# mcu.net
KiCad netlist of a schematic drawn in Altium Designer
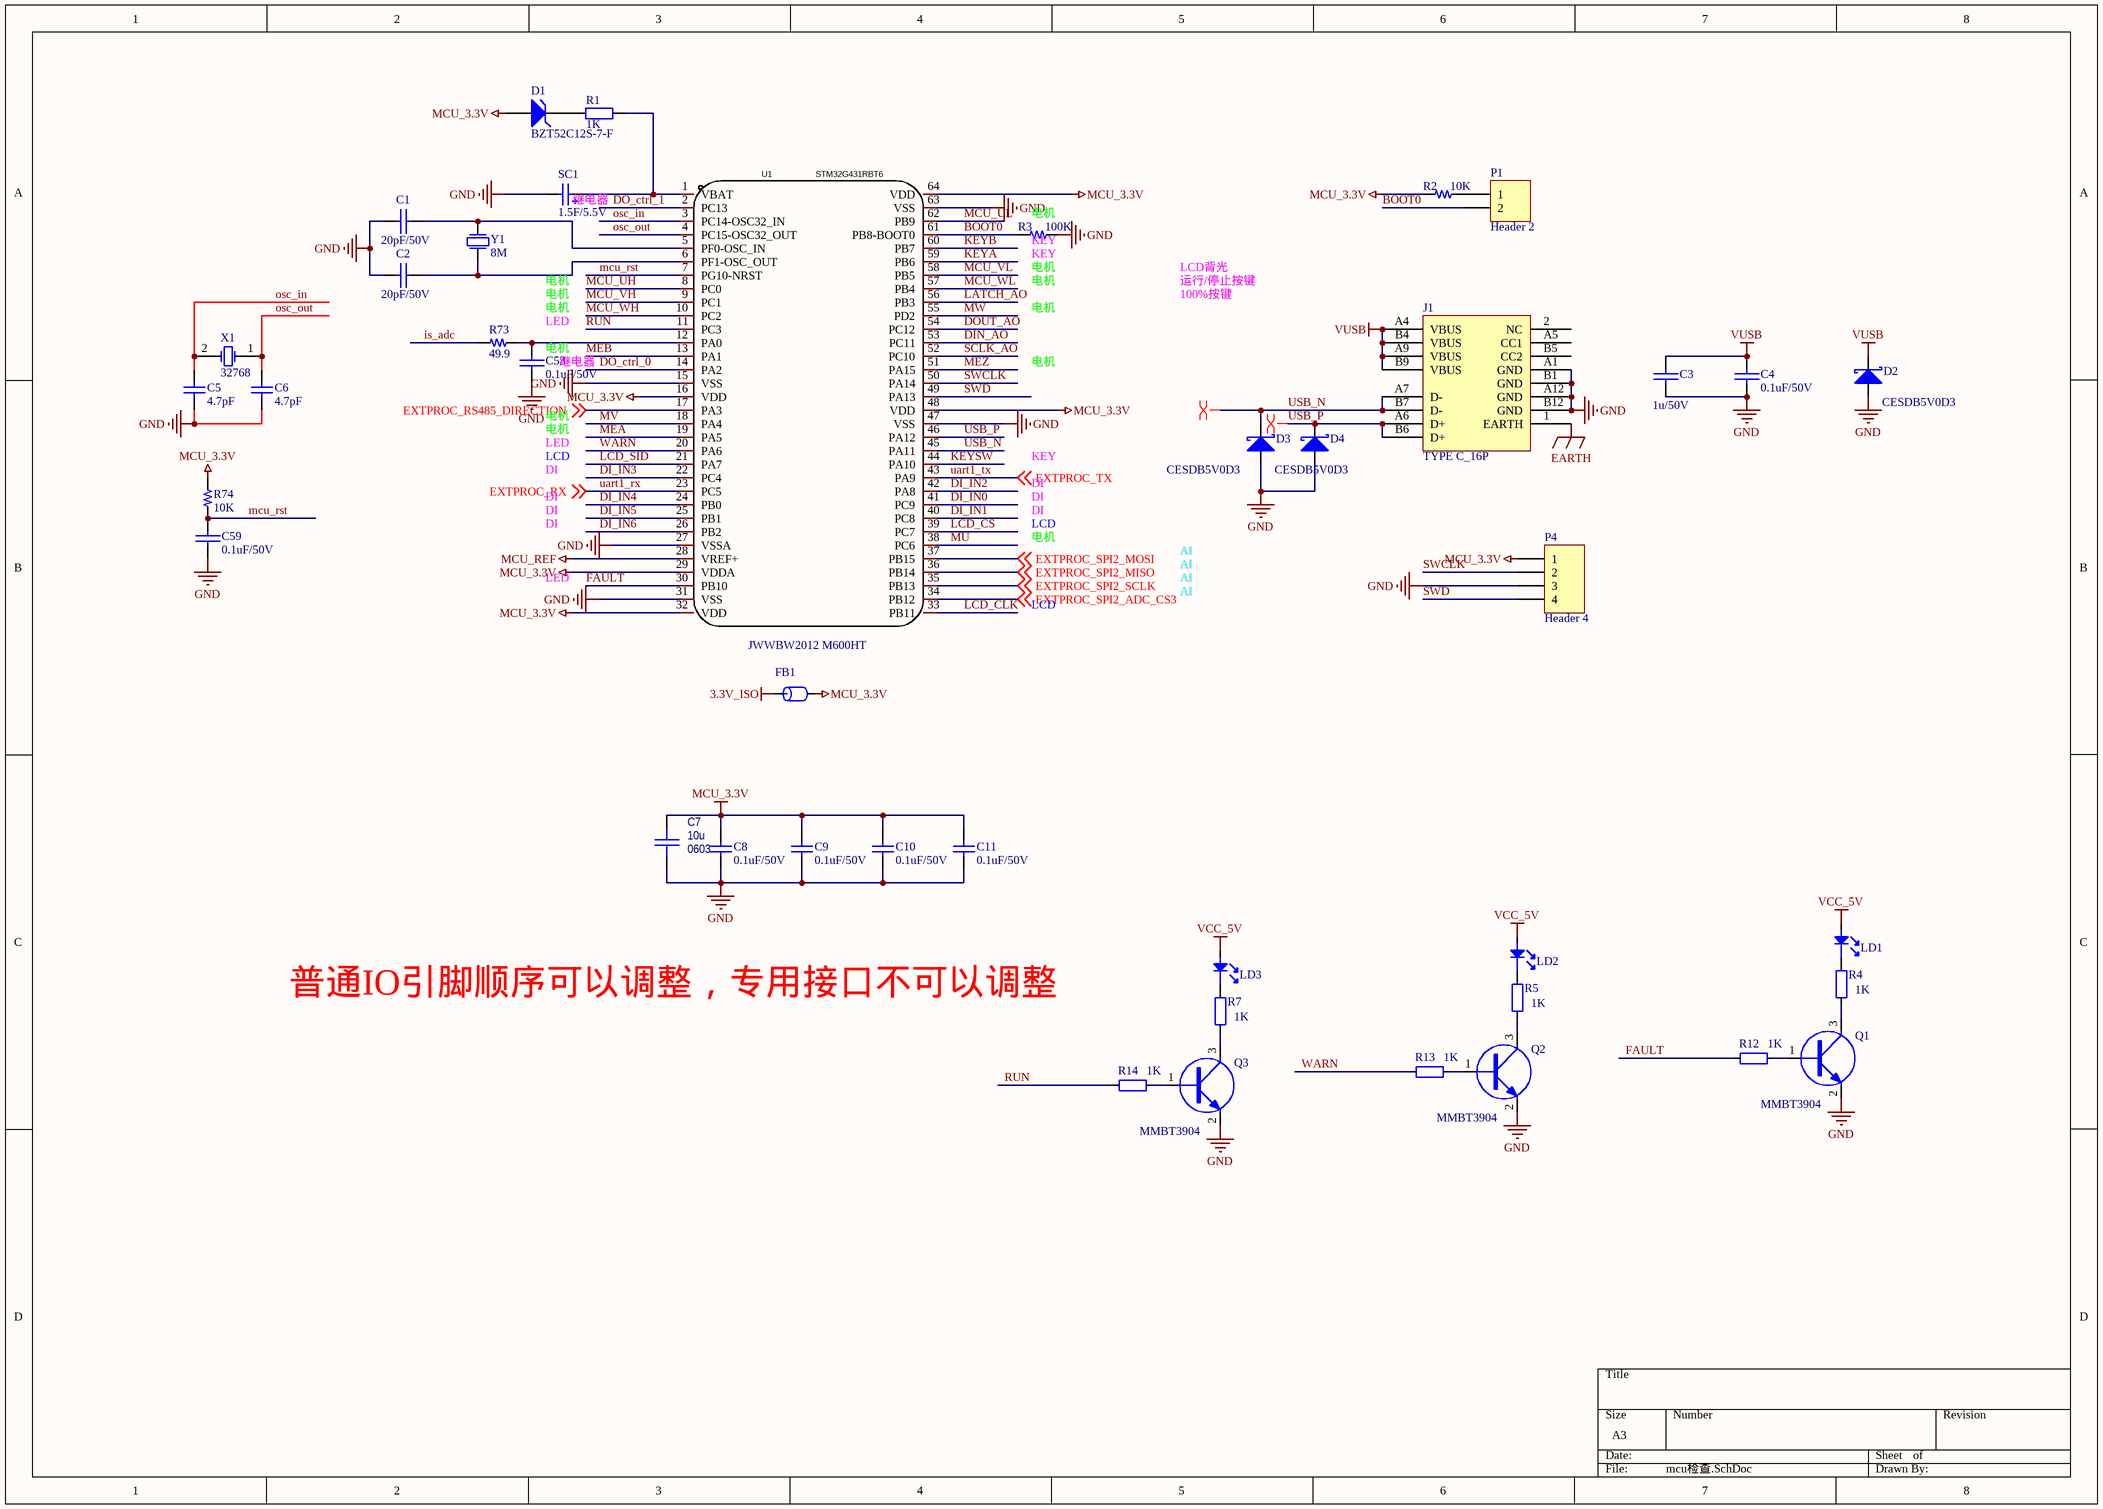
[diagram p0: mcu检查.SchDoc]

(export (version "E")
  (design (tool "Eeschema 10.0.6"))
  (components
    (comp (ref "C1")
      (value "20pF/50V")
      (footprint "0603C")
      (fields (field (name "Comment") "20pF/25V"))
      (libsource (lib "SM") (part "CAP"))
    )
    (comp (ref "C2")
      (value "20pF/50V")
      (footprint "0603C")
      (fields (field (name "Comment") "20pF/25V"))
      (libsource (lib "SM") (part "CAP"))
    )
    (comp (ref "C3")
      (value "1u/50V")
      (footprint "0603C")
      (fields (field (name "Comment") "1uF/25V"))
      (libsource (lib "SM") (part "CAP"))
    )
    (comp (ref "C4") (value "0.1uF/50V") (footprint "0603C") (libsource (lib "SM") (part "CAP")))
    (comp (ref "C5")
      (value "4.7pF")
      (footprint "0603C")
      (description "Capacitor")
      (fields (field (name "PUBLISHER") "Altium Limited"))
      (libsource (lib "Miscellaneous Devices") (part "Cap"))
    )
    (comp (ref "C6")
      (value "4.7pF")
      (footprint "0603C")
      (description "Capacitor")
      (fields (field (name "PUBLISHER") "Altium Limited"))
      (libsource (lib "Miscellaneous Devices") (part "Cap"))
    )
    (comp (ref "C7")
      (value "10u")
      (footprint "CAPC1608X092N_0603")
      (description "Capacitor, MLCC")
      (fields
        (field (name "MANUFACTURER") "Murata Electronics")
        (field (name "PARTNUMBER") "GRM188R61A106KE69D")
        (field (name "PACKAGE") "0603")
      )
      (libsource (lib "Karl") (part "Capacitor_0603"))
    )
    (comp (ref "C8")
      (value "0.1uF/50V")
      (footprint "0603C")
      (description "Capacitor")
      (fields (field (name "PUBLISHER") "Altium Limited"))
      (libsource (lib "Miscellaneous Devices") (part "Cap"))
    )
    (comp (ref "C9")
      (value "0.1uF/50V")
      (footprint "0603C")
      (description "Capacitor")
      (fields (field (name "PUBLISHER") "Altium Limited"))
      (libsource (lib "Miscellaneous Devices") (part "Cap"))
    )
    (comp (ref "C10")
      (value "0.1uF/50V")
      (footprint "0603C")
      (description "Capacitor")
      (fields (field (name "PUBLISHER") "Altium Limited"))
      (libsource (lib "Miscellaneous Devices") (part "Cap"))
    )
    (comp (ref "C11")
      (value "0.1uF/50V")
      (footprint "0603C")
      (description "Capacitor")
      (fields (field (name "PUBLISHER") "Altium Limited"))
      (libsource (lib "Miscellaneous Devices") (part "Cap"))
    )
    (comp (ref "C53") (value "0.1uF/50V") (footprint "0603C") (libsource (lib "SM") (part "CAP")))
    (comp (ref "C59") (value "0.1uF/50V") (footprint "0603C") (libsource (lib "SM") (part "CAP")))
    (comp (ref "D1")
      (value "BZT52C12S-7-F")
      (footprint "DIOD-SOD323-2_V")
      (libsource (lib "Bogen") (part "BZT52C12S-7-F"))
    )
    (comp (ref "D2") (value "CESDB5V0D3") (footprint "SOD323") (libsource (lib "*") (part "DIODE S")))
    (comp (ref "D3") (value "CESDB5V0D3") (footprint "SOD323") (libsource (lib "*") (part "DIODE S")))
    (comp (ref "D4") (value "CESDB5V0D3") (footprint "SOD323") (libsource (lib "*") (part "DIODE S")))
    (comp (ref "FB1")
      (value "JWWBW2012 M600HT")
      (footprint "0805R")
      (libsource (lib "Schlib_20110825") (part "FB"))
    )
    (comp (ref "J1")
      (value "TYPE C_16P")
      (footprint "TYPEC_16P")
      (libsource (lib "Schlib_20110825") (part "TYPE C_16P"))
    )
    (comp (ref "LD1")
      (value "LED_Green_19-217")
      (footprint "0603led")
      (libsource (lib "RC_M_D_00") (part "LED_Green_19-217"))
    )
    (comp (ref "LD2")
      (value "LED_Green_19-217")
      (footprint "0603led")
      (libsource (lib "RC_M_D_00") (part "LED_Green_19-217"))
    )
    (comp (ref "LD3")
      (value "LED_Green_19-217")
      (footprint "0603led")
      (libsource (lib "RC_M_D_00") (part "LED_Green_19-217"))
    )
    (comp (ref "P1")
      (value "Header 2")
      (footprint "HDR1X2")
      (fields (field (name "PUBLISHER") "Altium Limited"))
      (libsource (lib "Miscellaneous Connectors") (part "Header 2"))
    )
    (comp (ref "P4")
      (value "Header 4")
      (footprint "HDR1X4")
      (fields (field (name "PUBLISHER") "Altium Limited"))
      (libsource (lib "Miscellaneous Connectors") (part "Header 4"))
    )
    (comp (ref "Q1")
      (value "MMBT3904")
      (footprint "SOT23-3")
      (libsource (lib "CenLib") (part "NPN_MMBT3904"))
    )
    (comp (ref "Q2")
      (value "MMBT3904")
      (footprint "SOT23-3")
      (libsource (lib "CenLib") (part "NPN_MMBT3904"))
    )
    (comp (ref "Q3")
      (value "MMBT3904")
      (footprint "SOT23-3")
      (libsource (lib "CenLib") (part "NPN_MMBT3904"))
    )
    (comp (ref "R1") (value "1K") (footprint "0603R") (libsource (lib "MQlibrary") (part "Res0805M")))
    (comp (ref "R2") (value "10K") (footprint "0603R") (libsource (lib "JRJ_1") (part "R")))
    (comp (ref "R3") (value "100K") (footprint "0603R") (libsource (lib "JRJ_1") (part "R")))
    (comp (ref "R4") (value "1K") (footprint "0603r") (libsource (lib "RC_M_D_00") (part "RES0603")))
    (comp (ref "R5") (value "1K") (footprint "0603r") (libsource (lib "RC_M_D_00") (part "RES0603")))
    (comp (ref "R7") (value "1K") (footprint "0603r") (libsource (lib "RC_M_D_00") (part "RES0603")))
    (comp (ref "R12") (value "1K") (footprint "0603r") (libsource (lib "RC_M_D_00") (part "RES0603")))
    (comp (ref "R13") (value "1K") (footprint "0603r") (libsource (lib "RC_M_D_00") (part "RES0603")))
    (comp (ref "R14") (value "1K") (footprint "0603r") (libsource (lib "RC_M_D_00") (part "RES0603")))
    (comp (ref "R73") (value "49.9") (footprint "0603R") (libsource (lib "JRJ_1") (part "R")))
    (comp (ref "R74") (value "10K") (footprint "0603R") (libsource (lib "JRJ_1") (part "R")))
    (comp (ref "SC1")
      (value "1.5F/5.5V")
      (footprint "CAP-TH_DMS3R3224")
      (description "Polarized Capacitor (Axial)")
      (fields (field (name "PUBLISHER") "Altium Limited"))
      (libsource (lib "Miscellaneous Devices") (part "Cap Pol2"))
    )
    (comp (ref "U1")
      (value "STM32G431RBT6")
      (footprint "LQFP-64")
      (fields (field (name "MANUFACTURER") "ST(意法半导体)"))
      (libsource (lib "altium-import") (part "root_0_STM32G431RBT6_"))
    )
    (comp (ref "X1")
      (value "32768")
      (footprint "A")
      (description "Crystal Oscillator")
      (fields (field (name "PUBLISHER") "Altium Limited"))
      (libsource (lib "Miscellaneous Devices") (part "XTAL"))
    )
    (comp (ref "Y1") (value "8M") (footprint "CRAY_5032") (libsource (lib "") (part "XTAL_1")))
  )
  (nets
    (net (code "1") (name "/BOOT0") (class "Default")
      (node (ref "P1") (pin "2") (pinfunction "2_2") (pintype "passive"))
      (node (ref "R3") (pin "1") (pintype "passive"))
      (node (ref "U1") (pin "61") (pinfunction "PB8-BOOT0_61") (pintype "passive"))
    )
    (net (code "2") (name "/DIN_AO") (class "Default")
      (node (ref "U1") (pin "53") (pinfunction "PC11_53") (pintype "passive"))
    )
    (net (code "3") (name "/DI_IN0") (class "Default")
      (node (ref "U1") (pin "41") (pinfunction "PC9_41") (pintype "passive"))
    )
    (net (code "4") (name "/DI_IN1") (class "Default")
      (node (ref "U1") (pin "40") (pinfunction "PC8_40") (pintype "passive"))
    )
    (net (code "5") (name "/DI_IN2") (class "Default")
      (node (ref "U1") (pin "42") (pinfunction "PA8_42") (pintype "passive"))
    )
    (net (code "6") (name "/DI_IN3") (class "Default")
      (node (ref "U1") (pin "22") (pinfunction "PC4_22") (pintype "passive"))
    )
    (net (code "7") (name "/DI_IN4") (class "Default")
      (node (ref "U1") (pin "24") (pinfunction "PB0_24") (pintype "passive"))
    )
    (net (code "8") (name "/DI_IN5") (class "Default")
      (node (ref "U1") (pin "25") (pinfunction "PB1_25") (pintype "passive"))
    )
    (net (code "9") (name "/DI_IN6") (class "Default")
      (node (ref "U1") (pin "26") (pinfunction "PB2_26") (pintype "passive"))
    )
    (net (code "10") (name "/DOUT_AO") (class "Default")
      (node (ref "U1") (pin "54") (pinfunction "PC12_54") (pintype "passive"))
    )
    (net (code "11") (name "/DO_ctrl_0") (class "Default")
      (node (ref "U1") (pin "14") (pinfunction "PA2_14") (pintype "passive"))
    )
    (net (code "12") (name "/DO_ctrl_1") (class "Default")
      (node (ref "U1") (pin "2") (pinfunction "PC13_2") (pintype "passive"))
    )
    (net (code "13") (name "/FAULT") (class "Default")
      (node (ref "R12") (pin "1") (pinfunction "1_1") (pintype "passive"))
      (node (ref "U1") (pin "30") (pinfunction "PB10_30") (pintype "passive"))
    )
    (net (code "14") (name "/KEYA") (class "Default")
      (node (ref "U1") (pin "59") (pinfunction "PB6_59") (pintype "passive"))
    )
    (net (code "15") (name "/KEYB") (class "Default")
      (node (ref "U1") (pin "60") (pinfunction "PB7_60") (pintype "passive"))
    )
    (net (code "16") (name "/KEYSW") (class "Default")
      (node (ref "U1") (pin "44") (pinfunction "PA10_44") (pintype "passive"))
    )
    (net (code "17") (name "/LATCH_AO") (class "Default")
      (node (ref "U1") (pin "56") (pinfunction "PB3_56") (pintype "passive"))
    )
    (net (code "18") (name "/LCD_CLK") (class "Default")
      (node (ref "U1") (pin "33") (pinfunction "PB11_33") (pintype "passive"))
    )
    (net (code "19") (name "/LCD_CS") (class "Default")
      (node (ref "U1") (pin "39") (pinfunction "PC7_39") (pintype "passive"))
    )
    (net (code "20") (name "/LCD_SID") (class "Default")
      (node (ref "U1") (pin "21") (pinfunction "PA7_21") (pintype "passive"))
    )
    (net (code "21") (name "/MCU_UH") (class "Default")
      (node (ref "U1") (pin "8") (pinfunction "PC0_8") (pintype "passive"))
    )
    (net (code "22") (name "/MCU_UL") (class "Default")
      (node (ref "U1") (pin "62") (pinfunction "PB9_62") (pintype "passive"))
    )
    (net (code "23") (name "/MCU_VH") (class "Default")
      (node (ref "U1") (pin "9") (pinfunction "PC1_9") (pintype "passive"))
    )
    (net (code "24") (name "/MCU_VL") (class "Default")
      (node (ref "U1") (pin "58") (pinfunction "PB5_58") (pintype "passive"))
    )
    (net (code "25") (name "/MCU_WH") (class "Default")
      (node (ref "U1") (pin "10") (pinfunction "PC2_10") (pintype "passive"))
    )
    (net (code "26") (name "/MCU_WL") (class "Default")
      (node (ref "U1") (pin "57") (pinfunction "PB4_57") (pintype "passive"))
    )
    (net (code "27") (name "/MEA") (class "Default")
      (node (ref "U1") (pin "19") (pinfunction "PA5_19") (pintype "passive"))
    )
    (net (code "28") (name "/MEB") (class "Default")
      (node (ref "U1") (pin "13") (pinfunction "PA1_13") (pintype "passive"))
    )
    (net (code "29") (name "/MEZ") (class "Default")
      (node (ref "U1") (pin "51") (pinfunction "PA15_51") (pintype "passive"))
    )
    (net (code "30") (name "/MU") (class "Default")
      (node (ref "U1") (pin "38") (pinfunction "PC6_38") (pintype "passive"))
    )
    (net (code "31") (name "/MV") (class "Default")
      (node (ref "U1") (pin "18") (pinfunction "PA4_18") (pintype "passive"))
    )
    (net (code "32") (name "/MW") (class "Default")
      (node (ref "U1") (pin "55") (pinfunction "PD2_55") (pintype "passive"))
    )
    (net (code "33") (name "/RUN") (class "Default")
      (node (ref "R14") (pin "1") (pinfunction "1_1") (pintype "passive"))
      (node (ref "U1") (pin "11") (pinfunction "PC3_11") (pintype "passive"))
    )
    (net (code "34") (name "/SCLK_AO") (class "Default")
      (node (ref "U1") (pin "52") (pinfunction "PC10_52") (pintype "passive"))
    )
    (net (code "35") (name "/SWCLK") (class "Default")
      (node (ref "P4") (pin "2") (pinfunction "2_2") (pintype "passive"))
      (node (ref "U1") (pin "50") (pinfunction "PA14_50") (pintype "passive"))
    )
    (net (code "36") (name "/SWD") (class "Default")
      (node (ref "P4") (pin "4") (pinfunction "4_4") (pintype "passive"))
      (node (ref "U1") (pin "49") (pinfunction "PA13_49") (pintype "passive"))
    )
    (net (code "37") (name "/USB_N") (class "Default")
      (node (ref "D3") (pin "2") (pinfunction "K_2") (pintype "passive"))
      (node (ref "J1") (pin "A7") (pinfunction "D-_A7") (pintype "passive"))
      (node (ref "J1") (pin "B7") (pinfunction "D-_B7") (pintype "passive"))
      (node (ref "U1") (pin "45") (pinfunction "PA11_45") (pintype "passive"))
    )
    (net (code "38") (name "/USB_P") (class "Default")
      (node (ref "D4") (pin "2") (pinfunction "K_2") (pintype "passive"))
      (node (ref "J1") (pin "A6") (pinfunction "D+_A6") (pintype "passive"))
      (node (ref "J1") (pin "B6") (pinfunction "D+_B6") (pintype "passive"))
      (node (ref "U1") (pin "46") (pinfunction "PA12_46") (pintype "passive"))
    )
    (net (code "39") (name "/WARN") (class "Default")
      (node (ref "R13") (pin "1") (pinfunction "1_1") (pintype "passive"))
      (node (ref "U1") (pin "20") (pinfunction "PA6_20") (pintype "passive"))
    )
    (net (code "40") (name "/is_adc") (class "Default") (node (ref "R73") (pin "1") (pintype "passive")))
    (net (code "41") (name "/mcu_rst") (class "Default")
      (node (ref "C59") (pin "2") (pinfunction "2_2") (pintype "passive"))
      (node (ref "R74") (pin "2") (pintype "passive"))
      (node (ref "U1") (pin "7") (pinfunction "PG10-NRST_7") (pintype "passive"))
    )
    (net (code "42") (name "/osc_in") (class "Default")
      (node (ref "C5") (pin "1") (pinfunction "1_1") (pintype "passive"))
      (node (ref "U1") (pin "3") (pinfunction "PC14-OSC32_IN_3") (pintype "passive"))
      (node (ref "X1") (pin "2") (pinfunction "OSC2_2") (pintype "passive"))
    )
    (net (code "43") (name "/osc_out") (class "Default")
      (node (ref "C6") (pin "1") (pinfunction "1_1") (pintype "passive"))
      (node (ref "U1") (pin "4") (pinfunction "PC15-OSC32_OUT_4") (pintype "passive"))
      (node (ref "X1") (pin "1") (pinfunction "OSC1_1") (pintype "passive"))
    )
    (net (code "44") (name "3.3V_ISO") (class "Default") (node (ref "FB1") (pin "1") (pintype "passive")))
    (net (code "45") (name "EARTH") (class "Default")
      (node (ref "J1") (pin "1") (pinfunction "EARTH_1") (pintype "passive"))
    )
    (net (code "46") (name "EXTPROC_RS485_DIRECTION") (class "Default")
      (node (ref "U1") (pin "17") (pinfunction "PA3_17") (pintype "passive"))
    )
    (net (code "47") (name "EXTPROC_RX") (class "Default")
      (node (ref "U1") (pin "23") (pinfunction "PC5_23") (pintype "passive"))
    )
    (net (code "48") (name "EXTPROC_SPI2_ADC_CS3") (class "Default")
      (node (ref "U1") (pin "34") (pinfunction "PB12_34") (pintype "passive"))
    )
    (net (code "49") (name "EXTPROC_SPI2_MISO") (class "Default")
      (node (ref "U1") (pin "36") (pinfunction "PB14_36") (pintype "passive"))
    )
    (net (code "50") (name "EXTPROC_SPI2_MOSI") (class "Default")
      (node (ref "U1") (pin "37") (pinfunction "PB15_37") (pintype "passive"))
    )
    (net (code "51") (name "EXTPROC_SPI2_SCLK") (class "Default")
      (node (ref "U1") (pin "35") (pinfunction "PB13_35") (pintype "passive"))
    )
    (net (code "52") (name "EXTPROC_TX") (class "Default")
      (node (ref "U1") (pin "43") (pinfunction "PA9_43") (pintype "passive"))
    )
    (net (code "53") (name "GND") (class "Default")
      (node (ref "C1") (pin "2") (pinfunction "2_2") (pintype "passive"))
      (node (ref "C10") (pin "1") (pinfunction "1_1") (pintype "passive"))
      (node (ref "C11") (pin "1") (pinfunction "1_1") (pintype "passive"))
      (node (ref "C2") (pin "2") (pinfunction "2_2") (pintype "passive"))
      (node (ref "C3") (pin "1") (pinfunction "1_1") (pintype "passive"))
      (node (ref "C4") (pin "1") (pinfunction "1_1") (pintype "passive"))
      (node (ref "C5") (pin "2") (pinfunction "2_2") (pintype "passive"))
      (node (ref "C53") (pin "1") (pinfunction "1_1") (pintype "passive"))
      (node (ref "C59") (pin "1") (pinfunction "1_1") (pintype "passive"))
      (node (ref "C6") (pin "2") (pinfunction "2_2") (pintype "passive"))
      (node (ref "C7") (pin "2") (pinfunction "2_2") (pintype "passive"))
      (node (ref "C8") (pin "1") (pinfunction "1_1") (pintype "passive"))
      (node (ref "C9") (pin "1") (pinfunction "1_1") (pintype "passive"))
      (node (ref "D2") (pin "1") (pinfunction "A_1") (pintype "passive"))
      (node (ref "D3") (pin "1") (pinfunction "A_1") (pintype "passive"))
      (node (ref "D4") (pin "1") (pinfunction "A_1") (pintype "passive"))
      (node (ref "J1") (pin "A1") (pinfunction "GND_A1") (pintype "passive"))
      (node (ref "J1") (pin "A12") (pinfunction "GND_A12") (pintype "passive"))
      (node (ref "J1") (pin "B1") (pinfunction "GND_B1") (pintype "passive"))
      (node (ref "J1") (pin "B12") (pinfunction "GND_B12") (pintype "passive"))
      (node (ref "P4") (pin "3") (pinfunction "3_3") (pintype "passive"))
      (node (ref "Q1") (pin "2") (pinfunction "E_2") (pintype "passive"))
      (node (ref "Q2") (pin "2") (pinfunction "E_2") (pintype "passive"))
      (node (ref "Q3") (pin "2") (pinfunction "E_2") (pintype "passive"))
      (node (ref "R3") (pin "2") (pintype "passive"))
      (node (ref "SC1") (pin "2") (pinfunction "2_2") (pintype "passive"))
      (node (ref "U1") (pin "15") (pinfunction "VSS_15") (pintype "passive"))
      (node (ref "U1") (pin "27") (pinfunction "VSSA_27") (pintype "passive"))
      (node (ref "U1") (pin "31") (pinfunction "VSS_31") (pintype "passive"))
      (node (ref "U1") (pin "47") (pinfunction "VSS_47") (pintype "passive"))
      (node (ref "U1") (pin "63") (pinfunction "VSS_63") (pintype "passive"))
    )
    (net (code "54") (name "MCU_3.3V") (class "Default")
      (node (ref "C10") (pin "2") (pinfunction "2_2") (pintype "passive"))
      (node (ref "C11") (pin "2") (pinfunction "2_2") (pintype "passive"))
      (node (ref "C7") (pin "1") (pinfunction "1_1") (pintype "passive"))
      (node (ref "C8") (pin "2") (pinfunction "2_2") (pintype "passive"))
      (node (ref "C9") (pin "2") (pinfunction "2_2") (pintype "passive"))
      (node (ref "D1") (pin "1") (pinfunction "A_1") (pintype "passive"))
      (node (ref "FB1") (pin "2") (pintype "passive"))
      (node (ref "P4") (pin "1") (pinfunction "1_1") (pintype "passive"))
      (node (ref "R2") (pin "1") (pintype "passive"))
      (node (ref "R74") (pin "1") (pintype "passive"))
      (node (ref "U1") (pin "16") (pinfunction "VDD_16") (pintype "passive"))
      (node (ref "U1") (pin "29") (pinfunction "VDDA_29") (pintype "passive"))
      (node (ref "U1") (pin "32") (pinfunction "VDD_32") (pintype "passive"))
      (node (ref "U1") (pin "48") (pinfunction "VDD_48") (pintype "passive"))
      (node (ref "U1") (pin "64") (pinfunction "VDD_64") (pintype "passive"))
    )
    (net (code "55") (name "MCU_REF") (class "Default")
      (node (ref "U1") (pin "28") (pinfunction "VREF+_28") (pintype "passive"))
    )
    (net (code "56") (name "Net-(D1-K)") (class "Default")
      (node (ref "D1") (pin "2") (pinfunction "K_2") (pintype "passive"))
      (node (ref "R1") (pin "1") (pinfunction "1_1") (pintype "passive"))
    )
    (net (code "57") (name "Net-(LD1-Pad2)") (class "Default")
      (node (ref "LD1") (pin "2") (pinfunction "2_2") (pintype "passive"))
      (node (ref "R4") (pin "1") (pinfunction "1_1") (pintype "passive"))
    )
    (net (code "58") (name "Net-(LD2-Pad2)") (class "Default")
      (node (ref "LD2") (pin "2") (pinfunction "2_2") (pintype "passive"))
      (node (ref "R5") (pin "1") (pinfunction "1_1") (pintype "passive"))
    )
    (net (code "59") (name "Net-(LD3-Pad2)") (class "Default")
      (node (ref "LD3") (pin "2") (pinfunction "2_2") (pintype "passive"))
      (node (ref "R7") (pin "1") (pinfunction "1_1") (pintype "passive"))
    )
    (net (code "60") (name "Net-(P1-Pad1)") (class "Default")
      (node (ref "P1") (pin "1") (pinfunction "1_1") (pintype "passive"))
      (node (ref "R2") (pin "2") (pintype "passive"))
    )
    (net (code "61") (name "Net-(Q1-B)") (class "Default")
      (node (ref "Q1") (pin "1") (pinfunction "B_1") (pintype "passive"))
      (node (ref "R12") (pin "2") (pinfunction "2_2") (pintype "passive"))
    )
    (net (code "62") (name "Net-(Q1-C)") (class "Default")
      (node (ref "Q1") (pin "3") (pinfunction "C_3") (pintype "passive"))
      (node (ref "R4") (pin "2") (pinfunction "2_2") (pintype "passive"))
    )
    (net (code "63") (name "Net-(Q2-B)") (class "Default")
      (node (ref "Q2") (pin "1") (pinfunction "B_1") (pintype "passive"))
      (node (ref "R13") (pin "2") (pinfunction "2_2") (pintype "passive"))
    )
    (net (code "64") (name "Net-(Q2-C)") (class "Default")
      (node (ref "Q2") (pin "3") (pinfunction "C_3") (pintype "passive"))
      (node (ref "R5") (pin "2") (pinfunction "2_2") (pintype "passive"))
    )
    (net (code "65") (name "Net-(Q3-B)") (class "Default")
      (node (ref "Q3") (pin "1") (pinfunction "B_1") (pintype "passive"))
      (node (ref "R14") (pin "2") (pinfunction "2_2") (pintype "passive"))
    )
    (net (code "66") (name "Net-(Q3-C)") (class "Default")
      (node (ref "Q3") (pin "3") (pinfunction "C_3") (pintype "passive"))
      (node (ref "R7") (pin "2") (pinfunction "2_2") (pintype "passive"))
    )
    (net (code "67") (name "Net-(U1-PA0)") (class "Default")
      (node (ref "C53") (pin "2") (pinfunction "2_2") (pintype "passive"))
      (node (ref "R73") (pin "2") (pintype "passive"))
      (node (ref "U1") (pin "12") (pinfunction "PA0_12") (pintype "passive"))
    )
    (net (code "68") (name "Net-(U1-PF0-OSC_IN)") (class "Default")
      (node (ref "C1") (pin "1") (pinfunction "1_1") (pintype "passive"))
      (node (ref "U1") (pin "5") (pinfunction "PF0-OSC_IN_5") (pintype "passive"))
      (node (ref "Y1") (pin "1") (pinfunction "P1_1") (pintype "passive"))
    )
    (net (code "69") (name "Net-(U1-PF1-OSC_OUT)") (class "Default")
      (node (ref "C2") (pin "1") (pinfunction "1_1") (pintype "passive"))
      (node (ref "U1") (pin "6") (pinfunction "PF1-OSC_OUT_6") (pintype "passive"))
      (node (ref "Y1") (pin "2") (pinfunction "P2_2") (pintype "passive"))
    )
    (net (code "70") (name "Net-(U1-VBAT)") (class "Default")
      (node (ref "R1") (pin "2") (pinfunction "2_2") (pintype "passive"))
      (node (ref "SC1") (pin "1") (pinfunction "1_1") (pintype "passive"))
      (node (ref "U1") (pin "1") (pinfunction "VBAT_1") (pintype "passive"))
    )
    (net (code "71") (name "VCC_5V") (class "Default")
      (node (ref "LD1") (pin "1") (pinfunction "1_1") (pintype "passive"))
      (node (ref "LD2") (pin "1") (pinfunction "1_1") (pintype "passive"))
      (node (ref "LD3") (pin "1") (pinfunction "1_1") (pintype "passive"))
    )
    (net (code "72") (name "VUSB") (class "Default")
      (node (ref "C3") (pin "2") (pinfunction "2_2") (pintype "passive"))
      (node (ref "C4") (pin "2") (pinfunction "2_2") (pintype "passive"))
      (node (ref "D2") (pin "2") (pinfunction "K_2") (pintype "passive"))
      (node (ref "J1") (pin "A4") (pinfunction "VBUS_A4") (pintype "passive"))
      (node (ref "J1") (pin "A9") (pinfunction "VBUS_A9") (pintype "passive"))
      (node (ref "J1") (pin "B4") (pinfunction "VBUS_B4") (pintype "passive"))
      (node (ref "J1") (pin "B9") (pinfunction "VBUS_B9") (pintype "passive"))
    )
    (net (code "73") (name "unconnected-(J1-CC1-PadA5)") (class "Default")
      (node (ref "J1") (pin "A5") (pinfunction "CC1_A5") (pintype "passive"))
    )
    (net (code "74") (name "unconnected-(J1-CC2-PadB5)") (class "Default")
      (node (ref "J1") (pin "B5") (pinfunction "CC2_B5") (pintype "passive"))
    )
    (net (code "75") (name "unconnected-(J1-NC-Pad2)") (class "Default")
      (node (ref "J1") (pin "2") (pinfunction "NC_2") (pintype "passive"))
    )
  )
)
